# 3V3_Smooth.net
KiCad netlist of a schematic drawn in Altium Designer
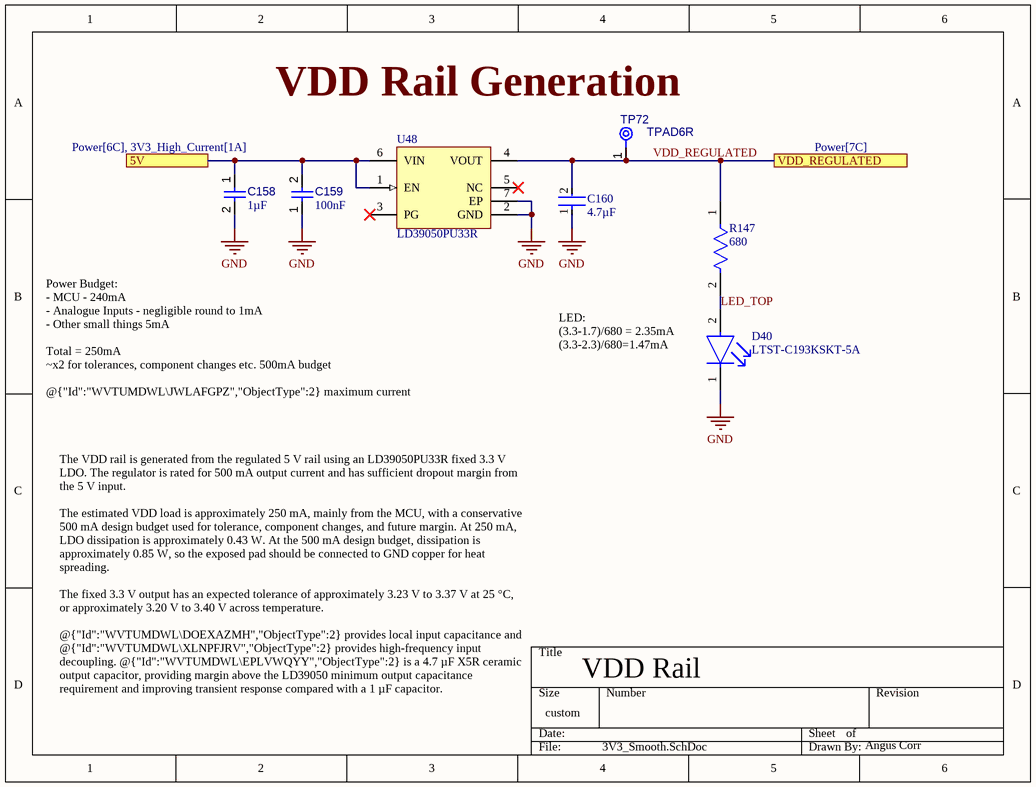
[diagram p0:  3V3_Smooth.SchDoc]

(export (version "E")
  (design (tool "Eeschema 10.0.6"))
  (components
    (comp (ref "C158")
      (value "1µF")
      (footprint "CAPC1608X90X40LL10T20")
      (description "Chip Capacitor, 1 uF, +/- 10%, 25 V, 0603 (1608 Metric)")
      (fields (field (name "TOLERANCE") "10%") (field (name "Comment") "Capacitor 1 uF +/- 10% 25 V 0603"))
      (libsource (lib "HIL RIG FYP") (part "CAP-NP-2"))
    )
    (comp (ref "C159")
      (value "100nF")
      (footprint "CAPC1608X90X40NL10T20")
      (description "Chip Capacitor, 100 nF, +/- 10%, 50 V, 0603 (1608 Metric)")
      (fields (field (name "TOLERANCE") "10%") (field (name "Comment") "Capacitor 100 nF +/-10% 50 V 0603"))
      (libsource (lib "HIL RIG FYP") (part "CAP-NP-2"))
    )
    (comp (ref "C160")
      (value "4.7µF")
      (footprint "FP-GRM21B-0_2-e0_2_0_7-MFG")
      (description "50V 4.7uF X7R ±10% 0805 Multilayer Ceramic Capacitors MLCC - SMD/SMT ROHS")
      (fields (field (name "TOLERANCE") "10%") (field (name "Comment") "GRM21BZ71H475KE15L"))
      (libsource (lib "HIL RIG FYP") (part "b4654b650e69147ec39a6b967a45e02"))
    )
    (comp (ref "D40")
      (value "LTST-C193KSKT-5A")
      (footprint "FP-LTST-C193KGKT-5A-MFG")
      (description "LED yellow 0603 wavelength 587~594.5nm light intensity 7.1~45mcd Front Mounting")
      (libsource (lib "HIL RIG FYP") (part "8706943c75ba83719d021d2fdc84c58"))
    )
    (comp (ref "R147")
      (value "680")
      (footprint "FP-CRCW0603-e3-IPC_C")
      (description "Fixed Resistor, Metal Glaze/Thick Film, 0.1W, 680ohm, 75V, 5% +/-Tol, Surface Mount, 0603")
      (fields (field (name "TOLERANCE") "5%") (field (name "Comment") "CRCW0603680RJNEA"))
      (libsource (lib "HIL RIG FYP") (part "1029c3af85768c4190bb7ad29bc67b5"))
    )
    (comp (ref "TP72")
      (value "TPAD6R")
      (footprint "TP06R")
      (description "0.6mm round")
      (libsource (lib "HIL RIG FYP") (part "CMP-001-0001-4"))
    )
    (comp (ref "U48")
      (value "LD39050PU33R")
      (footprint "DFN6D_L")
      (description "500 mA low quiescent current low noise voltage regulator")
      (libsource (lib "HIL RIG FYP") (part "PM-REG-LD39050-SQ7"))
    )
  )
  (nets
    (net (code "1") (name "/5V") (class "Default")
      (node (ref "C158") (pin "1") (pinfunction "1_1") (pintype "passive"))
      (node (ref "C159") (pin "2") (pinfunction "2_2") (pintype "passive"))
      (node (ref "U48") (pin "1") (pinfunction "EN_1") (pintype "input"))
      (node (ref "U48") (pin "6") (pinfunction "VIN_6") (pintype "power_in"))
    )
    (net (code "2") (name "/LED_TOP") (class "Default")
      (node (ref "D40") (pin "2") (pinfunction "A_2") (pintype "passive"))
      (node (ref "R147") (pin "2") (pinfunction "2_2") (pintype "passive"))
    )
    (net (code "3") (name "/VDD_REGULATED") (class "Default")
      (node (ref "C160") (pin "2") (pinfunction "2_2") (pintype "passive"))
      (node (ref "R147") (pin "1") (pinfunction "1_1") (pintype "passive"))
      (node (ref "TP72") (pin "1") (pinfunction "TP_1") (pintype "passive"))
      (node (ref "U48") (pin "4") (pinfunction "VOUT_4") (pintype "power_in"))
    )
    (net (code "4") (name "GND") (class "Default")
      (node (ref "C158") (pin "2") (pinfunction "2_2") (pintype "passive"))
      (node (ref "C159") (pin "1") (pinfunction "1_1") (pintype "passive"))
      (node (ref "C160") (pin "1") (pinfunction "1_1") (pintype "passive"))
      (node (ref "D40") (pin "1") (pinfunction "C_1") (pintype "passive"))
      (node (ref "U48") (pin "2") (pinfunction "GND_2") (pintype "power_in"))
      (node (ref "U48") (pin "7") (pinfunction "EP_7") (pintype "power_in"))
    )
    (net (code "5") (name "unconnected-(U48-NC-Pad5)") (class "Default")
      (node (ref "U48") (pin "5") (pinfunction "NC_5") (pintype "passive+no_connect"))
    )
    (net (code "6") (name "unconnected-(U48-PG-Pad3)") (class "Default")
      (node (ref "U48") (pin "3") (pinfunction "PG_3") (pintype "open_collector+no_connect"))
    )
  )
)
